# 3_cyber60-alps_mcu.net
KiCad netlist of a schematic drawn in Altium Designer
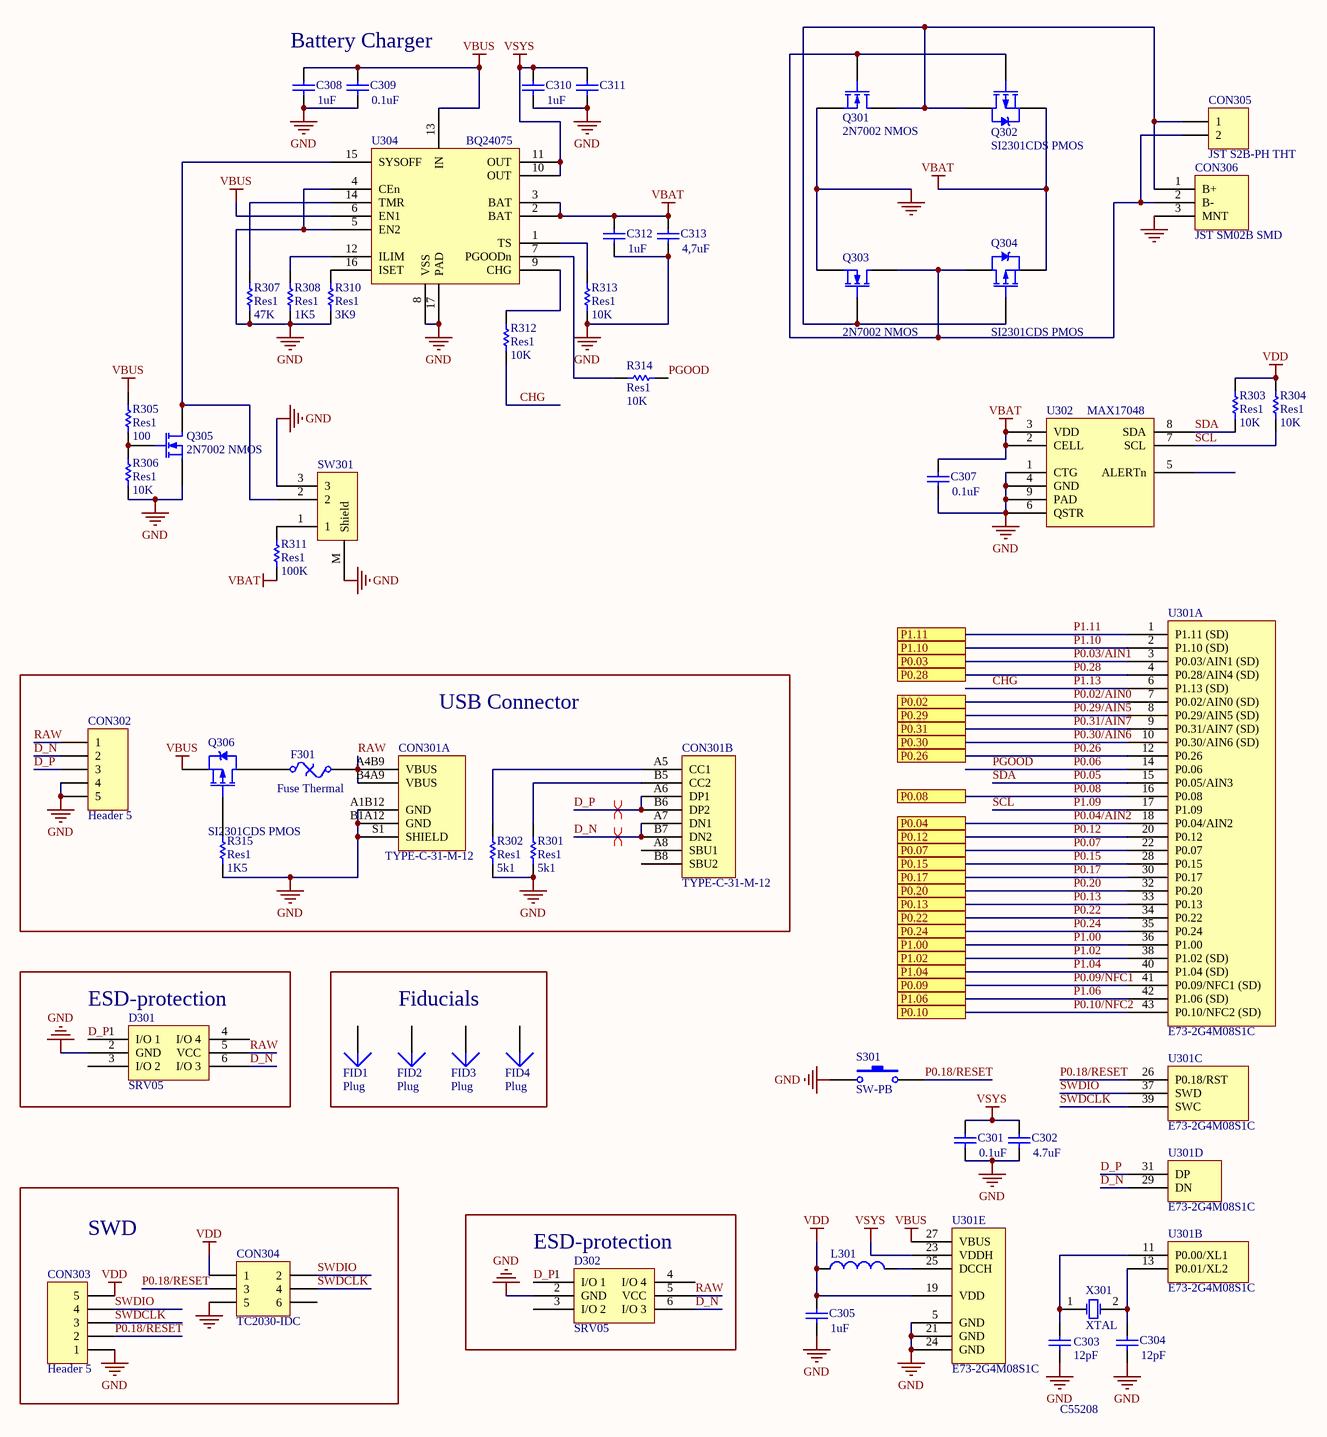
[diagram p0: 3_cyber60-alps_mcu.SchDoc]

(export (version "E")
  (design (tool "Eeschema 10.0.6"))
  (components
    (comp (ref "C301")
      (value "0.1uF")
      (footprint "C0603[1608]")
      (description "Capacitor")
      (fields (field (name "LCSC PART #") "C14663") (field (name "MRF.PART") "CC0603KRX7R9BB104"))
      (libsource (lib "Miscellaneous Devices") (part "Cap"))
    )
    (comp (ref "C302")
      (value "4.7uF")
      (footprint "C0603[1608]")
      (description "Capacitor")
      (fields (field (name "LCSC PART #") "C19666") (field (name "MRF.PART") "CL10A475KO8NNNC"))
      (libsource (lib "Miscellaneous Devices") (part "Cap"))
    )
    (comp (ref "C303")
      (value "12pF")
      (footprint "C0402[1005]")
      (description "Capacitor")
      (fields (field (name "LCSC PART #") "C1547") (field (name "MRF.PART") "0402CG120J500NT"))
      (libsource (lib "Miscellaneous Devices") (part "Cap"))
    )
    (comp (ref "C304")
      (value "12pF")
      (footprint "C0402[1005]")
      (description "Capacitor")
      (fields (field (name "LCSC PART #") "C1547") (field (name "MRF.PART") "0402CG120J500NT"))
      (libsource (lib "Miscellaneous Devices") (part "Cap"))
    )
    (comp (ref "C305")
      (value "1uF")
      (footprint "C0603[1608]")
      (description "Capacitor")
      (fields (field (name "LCSC PART #") "C15849") (field (name "MRF.PART") "CL10A105KB8NNNC"))
      (libsource (lib "Miscellaneous Devices") (part "Cap"))
    )
    (comp (ref "C307")
      (value "0.1uF")
      (footprint "C0603[1608]")
      (description "Capacitor")
      (fields (field (name "LCSC PART #") "C14663") (field (name "MRF.PART") "CC0603KRX7R9BB104"))
      (libsource (lib "Miscellaneous Devices") (part "Cap"))
    )
    (comp (ref "C308")
      (value "1uF")
      (footprint "C0603[1608]")
      (description "Capacitor")
      (fields (field (name "LCSC PART #") "C15849") (field (name "MRF.PART") "CL10A105KB8NNNC"))
      (libsource (lib "Miscellaneous Devices") (part "Cap"))
    )
    (comp (ref "C309")
      (value "0.1uF")
      (footprint "C0603[1608]")
      (description "Capacitor")
      (fields (field (name "LCSC PART #") "C14663") (field (name "MRF.PART") "CC0603KRX7R9BB104"))
      (libsource (lib "Miscellaneous Devices") (part "Cap"))
    )
    (comp (ref "C310")
      (value "1uF")
      (footprint "C0603[1608]")
      (description "Capacitor")
      (fields (field (name "LCSC PART #") "C15849") (field (name "MRF.PART") "CL10A105KB8NNNC"))
      (libsource (lib "Miscellaneous Devices") (part "Cap"))
    )
    (comp (ref "C311")
      (value "~")
      (footprint "C0603[1608]")
      (description "Capacitor")
      (fields (field (name "LCSC PART #") "C19666") (field (name "MRF.PART") "CL10A475KO8NNNC"))
      (libsource (lib "Miscellaneous Devices") (part "Cap"))
    )
    (comp (ref "C312")
      (value "1uF")
      (footprint "C0603[1608]")
      (description "Capacitor")
      (fields (field (name "LCSC PART #") "C15849") (field (name "MRF.PART") "CL10A105KB8NNNC"))
      (libsource (lib "Miscellaneous Devices") (part "Cap"))
    )
    (comp (ref "C313")
      (value "4,7uF")
      (footprint "C0603[1608]")
      (description "Capacitor")
      (fields (field (name "LCSC PART #") "C19666") (field (name "MRF.PART") "CL10A475KO8NNNC"))
      (libsource (lib "Miscellaneous Devices") (part "Cap"))
    )
    (comp (ref "CON301")
      (value "TYPE-C-31-M-12")
      (footprint "TYPE-C-31-M-12")
      (fields (field (name "MFG") "Korean Hroparts Elec") (field (name "LCSC PART #") "C165948"))
      (libsource (lib "Schlib1") (part "TYPE-C-31-M-12"))
    )
    (comp (ref "CON302")
      (value "Header 5")
      (footprint "UDB_COMBO_JST_MOLEX")
      (description "JST for USB daughter board")
      (fields (field (name "MFG") "JST Sales America Inc.") (field (name "LCSC PART #") "C160404"))
      (libsource (lib "Miscellaneous Connectors") (part "Header 5"))
    )
    (comp (ref "CON303")
      (value "Header 5")
      (footprint "HDR1X5")
      (description "Header, 5-Pin")
      (libsource (lib "") (part "Header 5_1"))
    )
    (comp (ref "CON304")
      (value "TC2030-IDC")
      (footprint "TC2030-IDC-NL")
      (description "Header, 3-Pin, Dual row")
      (libsource (lib "Miscellaneous Connectors") (part "Header 3X2"))
    )
    (comp (ref "CON305")
      (value "JST S2B-PH THT")
      (footprint "Keebs:JST S2B-PH-K(LF)(SN)")
      (description "Header, 2-Pin")
      (fields (field (name "LCSC PART #") "C265016") (field (name "MRF.PART") "S2B-PH-K(LF)(SN)"))
      (libsource (lib "Miscellaneous Connectors") (part "Header 2"))
    )
    (comp (ref "CON306")
      (value "JST SM02B SMD")
      (footprint "JST SM02B-SRSS-TB")
      (fields (field (name "LCSC PART #") "C160402") (field (name "MRF.PART") "SM02B-SRSS-TB(LF)(SN)"))
      (libsource (lib "Keebs") (part "JST S2B-PH-SM4-TB"))
    )
    (comp (ref "D301")
      (value "SRV05")
      (footprint "SOT-23-6")
      (fields (field (name "LCSC PART #") "C85364") (field (name "MRF.PART") "SRV05-4-P-T7"))
      (libsource (lib "Keebs") (part "SRV05"))
    )
    (comp (ref "D302")
      (value "SRV05")
      (footprint "SOT-23-6")
      (fields (field (name "LCSC PART #") "C85364") (field (name "MRF.PART") "SRV05-4-P-T7"))
      (libsource (lib "Keebs") (part "SRV05"))
    )
    (comp (ref "F301")
      (value "Fuse Thermal")
      (footprint "C1206[3216]")
      (description "Thermal Fuse")
      (fields (field (name "MFG") "Bel Fuse Inc.") (field (name "LCSC PART #") "C135338"))
      (libsource (lib "Miscellaneous Devices") (part "Fuse Thermal"))
    )
    (comp (ref "FID1")
      (value "Plug")
      (footprint "Fiducial_Nordic")
      (libsource (lib "Miscellaneous Connectors") (part "Plug"))
    )
    (comp (ref "FID2")
      (value "Plug")
      (footprint "Fiducial_Nordic")
      (libsource (lib "Miscellaneous Connectors") (part "Plug"))
    )
    (comp (ref "FID3")
      (value "Plug")
      (footprint "Fiducial_Nordic")
      (libsource (lib "Miscellaneous Connectors") (part "Plug"))
    )
    (comp (ref "FID4")
      (value "Plug")
      (footprint "Fiducial_Nordic")
      (libsource (lib "Miscellaneous Connectors") (part "Plug"))
    )
    (comp (ref "L301")
      (value "Inductor")
      (footprint "L0603[1608]")
      (fields (field (name "LCSC PART #") "C92982") (field (name "MRF.PART") "CBMF1608T100K"))
      (libsource (lib "Simulation Generic Components") (part "Inductor"))
    )
    (comp (ref "Q301")
      (value "2N7002 NMOS")
      (footprint "SOT-23-3")
      (description "N-Channel MOSFET")
      (fields (field (name "LCSC PART #") "C8545") (field (name "MRF.PART") "2N7002"))
      (libsource (lib "Miscellaneous Devices") (part "MOSFET-N"))
    )
    (comp (ref "Q302")
      (value "SI2301CDS PMOS")
      (footprint "SOT-23-3")
      (description "P-Channel Power MOSFET")
      (fields (field (name "MRF.PART") "SI2301CDS-T1-GE3") (field (name "LCSC PART #") "C10487"))
      (libsource (lib "Miscellaneous Devices") (part "PMOS-2"))
    )
    (comp (ref "Q303")
      (value "2N7002 NMOS")
      (footprint "SOT-23-3")
      (description "N-Channel MOSFET")
      (fields (field (name "LCSC PART #") "C8545") (field (name "MRF.PART") "2N7002"))
      (libsource (lib "Miscellaneous Devices") (part "MOSFET-N"))
    )
    (comp (ref "Q304")
      (value "SI2301CDS PMOS")
      (footprint "SOT-23-3")
      (description "P-Channel Power MOSFET")
      (fields (field (name "MRF.PART") "SI2301CDS-T1-GE3") (field (name "LCSC PART #") "C10487"))
      (libsource (lib "Miscellaneous Devices") (part "PMOS-2"))
    )
    (comp (ref "Q305")
      (value "2N7002 NMOS")
      (footprint "SOT-23-3")
      (description "N-Channel MOSFET")
      (fields (field (name "LCSC PART #") "C8545") (field (name "MRF.PART") "2N7002"))
      (libsource (lib "Miscellaneous Devices") (part "MOSFET-N"))
    )
    (comp (ref "Q306")
      (value "SI2301CDS PMOS")
      (footprint "SOT-23-3")
      (description "P-Channel Power MOSFET")
      (fields (field (name "MRF.PART") "SI2301CDS-T1-GE3") (field (name "LCSC PART #") "C10487"))
      (libsource (lib "Miscellaneous Devices") (part "PMOS-2"))
    )
    (comp (ref "R301")
      (value "Res1")
      (footprint "R0603[1608]")
      (description "Resistor")
      (fields
        (field (name "ALTIUM_VALUE") "5k1")
        (field (name "MFG") "Panasonic Electronic Components")
        (field (name "LCSC PART #") "C23186")
      )
      (libsource (lib "Miscellaneous Devices") (part "Res1"))
    )
    (comp (ref "R302")
      (value "Res1")
      (footprint "R0603[1608]")
      (description "Resistor")
      (fields
        (field (name "ALTIUM_VALUE") "5k1")
        (field (name "MFG") "Panasonic Electronic Components")
        (field (name "LCSC PART #") "C23186")
      )
      (libsource (lib "Miscellaneous Devices") (part "Res1"))
    )
    (comp (ref "R303")
      (value "Res1")
      (footprint "R0603[1608]")
      (description "Resistor")
      (fields
        (field (name "ALTIUM_VALUE") "10K")
        (field (name "LCSC PART #") "C25804")
        (field (name "MRF.PART") "0603WAF1002T5E")
      )
      (libsource (lib "Miscellaneous Devices") (part "Res1"))
    )
    (comp (ref "R304")
      (value "Res1")
      (footprint "R0603[1608]")
      (description "Resistor")
      (fields
        (field (name "ALTIUM_VALUE") "10K")
        (field (name "LCSC PART #") "C25804")
        (field (name "MRF.PART") "0603WAF1002T5E")
      )
      (libsource (lib "Miscellaneous Devices") (part "Res1"))
    )
    (comp (ref "R305")
      (value "Res1")
      (footprint "R0603[1608]")
      (description "Resistor")
      (fields
        (field (name "ALTIUM_VALUE") "100")
        (field (name "LCSC PART #") "C22775")
        (field (name "MRF.PART") "0603WAF1000T5E")
      )
      (libsource (lib "Miscellaneous Devices") (part "Res1"))
    )
    (comp (ref "R306")
      (value "Res1")
      (footprint "R0603[1608]")
      (description "Resistor")
      (fields
        (field (name "ALTIUM_VALUE") "10K")
        (field (name "LCSC PART #") "C25804")
        (field (name "MRF.PART") "0603WAF1002T5E")
      )
      (libsource (lib "Miscellaneous Devices") (part "Res1"))
    )
    (comp (ref "R307")
      (value "Res1")
      (footprint "R0603[1608]")
      (description "Resistor")
      (fields
        (field (name "ALTIUM_VALUE") "47K")
        (field (name "LCSC PART #") "C25819")
        (field (name "MRF.PART") "0603WAF4702T5E")
      )
      (libsource (lib "Miscellaneous Devices") (part "Res1"))
    )
    (comp (ref "R308")
      (value "Res1")
      (footprint "R0603[1608]")
      (description "Resistor")
      (fields
        (field (name "ALTIUM_VALUE") "1K5")
        (field (name "LCSC PART #") "C22843")
        (field (name "MRF.PART") "0603WAF1501T5E")
      )
      (libsource (lib "Miscellaneous Devices") (part "Res1"))
    )
    (comp (ref "R310")
      (value "Res1")
      (footprint "R0603[1608]")
      (description "Resistor")
      (fields
        (field (name "ALTIUM_VALUE") "3K9")
        (field (name "LCSC PART #") "C23018")
        (field (name "MRF.PART") "0603WAF3901T5E")
      )
      (libsource (lib "Miscellaneous Devices") (part "Res1"))
    )
    (comp (ref "R311")
      (value "Res1")
      (footprint "R0603[1608]")
      (description "Resistor")
      (fields
        (field (name "ALTIUM_VALUE") "100K")
        (field (name "LCSC PART #") "C25804")
        (field (name "MRF.PART") "0603WAF1002T5E")
      )
      (libsource (lib "Miscellaneous Devices") (part "Res1"))
    )
    (comp (ref "R312")
      (value "Res1")
      (footprint "R0603[1608]")
      (description "Resistor")
      (fields
        (field (name "ALTIUM_VALUE") "10K")
        (field (name "LCSC PART #") "C25804")
        (field (name "MRF.PART") "0603WAF1002T5E")
      )
      (libsource (lib "Miscellaneous Devices") (part "Res1"))
    )
    (comp (ref "R313")
      (value "Res1")
      (footprint "R0603[1608]")
      (description "Resistor")
      (fields
        (field (name "ALTIUM_VALUE") "10K")
        (field (name "LCSC PART #") "C25804")
        (field (name "MRF.PART") "0603WAF1002T5E")
      )
      (libsource (lib "Miscellaneous Devices") (part "Res1"))
    )
    (comp (ref "R314")
      (value "Res1")
      (footprint "R0603[1608]")
      (description "Resistor")
      (fields
        (field (name "ALTIUM_VALUE") "10K")
        (field (name "LCSC PART #") "C25804")
        (field (name "MRF.PART") "0603WAF1002T5E")
      )
      (libsource (lib "Miscellaneous Devices") (part "Res1"))
    )
    (comp (ref "R315")
      (value "Res1")
      (footprint "R0603[1608]")
      (description "Resistor")
      (fields
        (field (name "ALTIUM_VALUE") "1K5")
        (field (name "LCSC PART #") "C22843")
        (field (name "MRF.PART") "0603WAF1501T5E")
      )
      (libsource (lib "Miscellaneous Devices") (part "Res1"))
    )
    (comp (ref "S301")
      (value "SW-PB")
      (footprint "XKB Switch")
      (description "Switch")
      (fields (field (name "MRF.PART") "TS-1187A-C-D-B") (field (name "LCSC PART #") "C318888"))
      (libsource (lib "Miscellaneous Devices") (part "SW-PB"))
    )
    (comp (ref "SW301")
      (value "Korean Hroparts Elec K3-1296S-E2")
      (footprint "Korean Hroparts Elec K3-1296S-E2")
      (fields (field (name "LCSC PART #") "C136659"))
      (libsource (lib "Keebs") (part "Korean Hroparts Elec K3-1296S-E2"))
    )
    (comp (ref "U301")
      (value "E73-2G4M08S1C")
      (footprint "E73-2G4M08S1C")
      (fields (field (name "LCSC PART #") "C356849"))
      (libsource (lib "Keebs") (part "E73-2G4M08S1C"))
    )
    (comp (ref "U302")
      (value "MAX17048")
      (footprint "8TDFN")
      (fields (field (name "LCSC PART #") "C2682616") (field (name "MRF.PART") "MAX17048G+T10"))
      (libsource (lib "Keebs") (part "MAX17048"))
    )
    (comp (ref "U304")
      (value "BQ24075")
      (footprint "QFN16")
      (fields (field (name "LCSC PART #") "C15464") (field (name "MRF.PART") "BQ24075RGTR"))
      (libsource (lib "Keebs") (part "BQ24075"))
    )
    (comp (ref "X301")
      (value "XTAL")
      (footprint "XTAL-2012")
      (description "Crystal Oscillator")
      (fields (field (name "LCSC PART #") "C55208") (field (name "MRF.PART") "X1A0000610002"))
      (libsource (lib "Miscellaneous Devices") (part "XTAL"))
    )
  )
  (nets
    (net (code "1") (name "/CHG") (class "Default")
      (node (ref "R312") (pin "2") (pinfunction "2_2") (pintype "passive"))
      (node (ref "U301") (pin "6") (pinfunction "P1.13_(SD)_6") (pintype "passive"))
    )
    (net (code "2") (name "/D_N") (class "Default")
      (node (ref "CON301") (pin "A7") (pinfunction "DN1_A7") (pintype "passive"))
      (node (ref "CON301") (pin "B7") (pinfunction "DN2_B7") (pintype "passive"))
      (node (ref "CON302") (pin "2") (pinfunction "2_2") (pintype "passive"))
      (node (ref "D301") (pin "6") (pinfunction "I/O_3_6") (pintype "passive"))
      (node (ref "D302") (pin "6") (pinfunction "I/O_3_6") (pintype "passive"))
      (node (ref "U301") (pin "29") (pinfunction "DN_29") (pintype "passive"))
    )
    (net (code "3") (name "/D_P") (class "Default")
      (node (ref "CON301") (pin "A6") (pinfunction "DP1_A6") (pintype "passive"))
      (node (ref "CON301") (pin "B6") (pinfunction "DP2_B6") (pintype "passive"))
      (node (ref "CON302") (pin "3") (pinfunction "3_3") (pintype "passive"))
      (node (ref "D301") (pin "1") (pinfunction "I/O_1_1") (pintype "passive"))
      (node (ref "D302") (pin "1") (pinfunction "I/O_1_1") (pintype "passive"))
      (node (ref "U301") (pin "31") (pinfunction "DP_31") (pintype "passive"))
    )
    (net (code "4") (name "/P0.02{slash}AIN0") (class "Default")
      (node (ref "U301") (pin "7") (pinfunction "P0.02/AIN0_(SD)_7") (pintype "passive"))
    )
    (net (code "5") (name "/P0.03{slash}AIN1") (class "Default")
      (node (ref "U301") (pin "3") (pinfunction "P0.03/AIN1_(SD)_3") (pintype "passive"))
    )
    (net (code "6") (name "/P0.04{slash}AIN2") (class "Default")
      (node (ref "U301") (pin "18") (pinfunction "P0.04/AIN2_18") (pintype "passive"))
    )
    (net (code "7") (name "/P0.05") (class "Default")
      (node (ref "R303") (pin "2") (pinfunction "2_2") (pintype "passive"))
      (node (ref "U301") (pin "15") (pinfunction "P0.05/AIN3_15") (pintype "passive"))
      (node (ref "U302") (pin "8") (pinfunction "SDA_8") (pintype "passive"))
    )
    (net (code "8") (name "/P0.06") (class "Default")
      (node (ref "R314") (pin "2") (pinfunction "2_2") (pintype "passive"))
      (node (ref "U301") (pin "14") (pinfunction "P0.06_14") (pintype "passive"))
    )
    (net (code "9") (name "/P0.07") (class "Default")
      (node (ref "U301") (pin "22") (pinfunction "P0.07_22") (pintype "passive"))
    )
    (net (code "10") (name "/P0.08") (class "Default")
      (node (ref "U301") (pin "16") (pinfunction "P0.08_16") (pintype "passive"))
    )
    (net (code "11") (name "/P0.09{slash}NFC1") (class "Default")
      (node (ref "U301") (pin "41") (pinfunction "P0.09/NFC1_(SD)_41") (pintype "passive"))
    )
    (net (code "12") (name "/P0.10{slash}NFC2") (class "Default")
      (node (ref "U301") (pin "43") (pinfunction "P0.10/NFC2_(SD)_43") (pintype "passive"))
    )
    (net (code "13") (name "/P0.12") (class "Default")
      (node (ref "U301") (pin "20") (pinfunction "P0.12_20") (pintype "passive"))
    )
    (net (code "14") (name "/P0.13") (class "Default")
      (node (ref "U301") (pin "33") (pinfunction "P0.13_33") (pintype "passive"))
    )
    (net (code "15") (name "/P0.15") (class "Default")
      (node (ref "U301") (pin "28") (pinfunction "P0.15_28") (pintype "passive"))
    )
    (net (code "16") (name "/P0.17") (class "Default")
      (node (ref "U301") (pin "30") (pinfunction "P0.17_30") (pintype "passive"))
    )
    (net (code "17") (name "/P0.18{slash}RESET") (class "Default")
      (node (ref "CON303") (pin "2") (pinfunction "2_2") (pintype "passive"))
      (node (ref "CON304") (pin "3") (pinfunction "3_3") (pintype "passive"))
      (node (ref "S301") (pin "2") (pinfunction "2_2") (pintype "passive"))
      (node (ref "U301") (pin "26") (pinfunction "P0.18/RST_26") (pintype "passive"))
    )
    (net (code "18") (name "/P0.20") (class "Default")
      (node (ref "U301") (pin "32") (pinfunction "P0.20_32") (pintype "passive"))
    )
    (net (code "19") (name "/P0.22") (class "Default")
      (node (ref "U301") (pin "34") (pinfunction "P0.22_34") (pintype "passive"))
    )
    (net (code "20") (name "/P0.24") (class "Default")
      (node (ref "U301") (pin "35") (pinfunction "P0.24_35") (pintype "passive"))
    )
    (net (code "21") (name "/P0.26") (class "Default")
      (node (ref "U301") (pin "12") (pinfunction "P0.26_12") (pintype "passive"))
    )
    (net (code "22") (name "/P0.28") (class "Default")
      (node (ref "U301") (pin "4") (pinfunction "P0.28/AIN4_(SD)_4") (pintype "passive"))
    )
    (net (code "23") (name "/P0.29{slash}AIN5") (class "Default")
      (node (ref "U301") (pin "8") (pinfunction "P0.29/AIN5_(SD)_8") (pintype "passive"))
    )
    (net (code "24") (name "/P0.30{slash}AIN6") (class "Default")
      (node (ref "U301") (pin "10") (pinfunction "P0.30/AIN6_(SD)_10") (pintype "passive"))
    )
    (net (code "25") (name "/P0.31{slash}AIN7") (class "Default")
      (node (ref "U301") (pin "9") (pinfunction "P0.31/AIN7_(SD)_9") (pintype "passive"))
    )
    (net (code "26") (name "/P1.00") (class "Default")
      (node (ref "U301") (pin "36") (pinfunction "P1.00_36") (pintype "passive"))
    )
    (net (code "27") (name "/P1.02") (class "Default")
      (node (ref "U301") (pin "38") (pinfunction "P1.02_(SD)_38") (pintype "passive"))
    )
    (net (code "28") (name "/P1.04") (class "Default")
      (node (ref "U301") (pin "40") (pinfunction "P1.04_(SD)_40") (pintype "passive"))
    )
    (net (code "29") (name "/P1.06") (class "Default")
      (node (ref "U301") (pin "42") (pinfunction "P1.06_(SD)_42") (pintype "passive"))
    )
    (net (code "30") (name "/P1.09") (class "Default")
      (node (ref "R304") (pin "2") (pinfunction "2_2") (pintype "passive"))
      (node (ref "U301") (pin "17") (pinfunction "P1.09_17") (pintype "passive"))
      (node (ref "U302") (pin "7") (pinfunction "SCL_7") (pintype "passive"))
    )
    (net (code "31") (name "/P1.10") (class "Default")
      (node (ref "U301") (pin "2") (pinfunction "P1.10_(SD)_2") (pintype "passive"))
    )
    (net (code "32") (name "/P1.11") (class "Default")
      (node (ref "U301") (pin "1") (pinfunction "P1.11_(SD)_1") (pintype "passive"))
    )
    (net (code "33") (name "/RAW") (class "Default")
      (node (ref "CON301") (pin "A4B9") (pinfunction "VBUS_A4B9") (pintype "passive"))
      (node (ref "CON301") (pin "B4A9") (pinfunction "VBUS_B4A9") (pintype "passive"))
      (node (ref "CON302") (pin "1") (pinfunction "1_1") (pintype "passive"))
      (node (ref "D301") (pin "5") (pinfunction "VCC_5") (pintype "passive"))
      (node (ref "D302") (pin "5") (pinfunction "VCC_5") (pintype "passive"))
      (node (ref "F301") (pin "2") (pinfunction "2_2") (pintype "passive"))
    )
    (net (code "34") (name "/SWDCLK") (class "Default")
      (node (ref "CON303") (pin "3") (pinfunction "3_3") (pintype "passive"))
      (node (ref "CON304") (pin "4") (pinfunction "4_4") (pintype "passive"))
      (node (ref "U301") (pin "39") (pinfunction "SWC_39") (pintype "passive"))
    )
    (net (code "35") (name "/SWDIO") (class "Default")
      (node (ref "CON303") (pin "4") (pinfunction "4_4") (pintype "passive"))
      (node (ref "CON304") (pin "2") (pinfunction "2_2") (pintype "passive"))
      (node (ref "U301") (pin "37") (pinfunction "SWD_37") (pintype "passive"))
    )
    (net (code "36") (name "GND") (class "Default")
      (node (ref "C301") (pin "1") (pinfunction "1_1") (pintype "passive"))
      (node (ref "C302") (pin "1") (pinfunction "1_1") (pintype "passive"))
      (node (ref "C303") (pin "1") (pinfunction "1_1") (pintype "passive"))
      (node (ref "C304") (pin "1") (pinfunction "1_1") (pintype "passive"))
      (node (ref "C305") (pin "1") (pinfunction "1_1") (pintype "passive"))
      (node (ref "C307") (pin "1") (pinfunction "1_1") (pintype "passive"))
      (node (ref "C308") (pin "1") (pinfunction "1_1") (pintype "passive"))
      (node (ref "C309") (pin "1") (pinfunction "1_1") (pintype "passive"))
      (node (ref "C310") (pin "1") (pinfunction "1_1") (pintype "passive"))
      (node (ref "C311") (pin "1") (pinfunction "1_1") (pintype "passive"))
      (node (ref "C312") (pin "1") (pinfunction "1_1") (pintype "passive"))
      (node (ref "C313") (pin "1") (pinfunction "1_1") (pintype "passive"))
      (node (ref "CON301") (pin "A1B12") (pinfunction "GND_A1B12") (pintype "passive"))
      (node (ref "CON301") (pin "B1A12") (pinfunction "GND_B1A12") (pintype "passive"))
      (node (ref "CON301") (pin "S1") (pinfunction "SHIELD_S1") (pintype "passive"))
      (node (ref "CON302") (pin "4") (pinfunction "4_4") (pintype "passive"))
      (node (ref "CON302") (pin "5") (pinfunction "5_5") (pintype "passive"))
      (node (ref "CON303") (pin "1") (pinfunction "1_1") (pintype "passive"))
      (node (ref "CON304") (pin "5") (pinfunction "5_5") (pintype "passive"))
      (node (ref "CON306") (pin "3") (pinfunction "MNT_3") (pintype "passive"))
      (node (ref "D301") (pin "2") (pinfunction "GND_2") (pintype "passive"))
      (node (ref "D302") (pin "2") (pinfunction "GND_2") (pintype "passive"))
      (node (ref "Q301") (pin "2") (pinfunction "S_2") (pintype "passive"))
      (node (ref "Q303") (pin "2") (pinfunction "S_2") (pintype "passive"))
      (node (ref "Q305") (pin "2") (pinfunction "S_2") (pintype "passive"))
      (node (ref "R301") (pin "2") (pinfunction "2_2") (pintype "passive"))
      (node (ref "R302") (pin "2") (pinfunction "2_2") (pintype "passive"))
      (node (ref "R306") (pin "2") (pinfunction "2_2") (pintype "passive"))
      (node (ref "R307") (pin "2") (pinfunction "2_2") (pintype "passive"))
      (node (ref "R308") (pin "2") (pinfunction "2_2") (pintype "passive"))
      (node (ref "R310") (pin "2") (pinfunction "2_2") (pintype "passive"))
      (node (ref "R313") (pin "2") (pinfunction "2_2") (pintype "passive"))
      (node (ref "R315") (pin "2") (pinfunction "2_2") (pintype "passive"))
      (node (ref "S301") (pin "1") (pinfunction "1_1") (pintype "passive"))
      (node (ref "SW301") (pin "3") (pinfunction "3_3") (pintype "passive"))
      (node (ref "SW301") (pin "M") (pinfunction "Shield_M") (pintype "passive"))
      (node (ref "U301") (pin "21") (pinfunction "GND_21") (pintype "passive"))
      (node (ref "U301") (pin "24") (pinfunction "GND_24") (pintype "passive"))
      (node (ref "U301") (pin "5") (pinfunction "GND_5") (pintype "passive"))
      (node (ref "U302") (pin "1") (pinfunction "CTG_1") (pintype "passive"))
      (node (ref "U302") (pin "4") (pinfunction "GND_4") (pintype "passive"))
      (node (ref "U302") (pin "6") (pinfunction "QSTR_6") (pintype "passive"))
      (node (ref "U302") (pin "9") (pinfunction "PAD_9") (pintype "passive"))
      (node (ref "U304") (pin "17") (pinfunction "PAD_17") (pintype "passive"))
      (node (ref "U304") (pin "4") (pinfunction "CEn_4") (pintype "passive"))
      (node (ref "U304") (pin "5") (pinfunction "EN2_5") (pintype "passive"))
      (node (ref "U304") (pin "8") (pinfunction "VSS_8") (pintype "passive"))
    )
    (net (code "37") (name "Net-(CON301B-CC1)") (class "Default")
      (node (ref "CON301") (pin "A5") (pinfunction "CC1_A5") (pintype "passive"))
      (node (ref "R302") (pin "1") (pinfunction "1_1") (pintype "passive"))
    )
    (net (code "38") (name "Net-(CON301B-CC2)") (class "Default")
      (node (ref "CON301") (pin "B5") (pinfunction "CC2_B5") (pintype "passive"))
      (node (ref "R301") (pin "1") (pinfunction "1_1") (pintype "passive"))
    )
    (net (code "39") (name "Net-(CON306-B+)") (class "Default")
      (node (ref "CON305") (pin "1") (pinfunction "1_1") (pintype "passive"))
      (node (ref "CON306") (pin "1") (pinfunction "B+_1") (pintype "passive"))
      (node (ref "Q301") (pin "3") (pinfunction "D_3") (pintype "passive"))
      (node (ref "Q302") (pin "3") (pinfunction "D_3") (pintype "passive"))
      (node (ref "Q303") (pin "1") (pinfunction "G_1") (pintype "passive"))
      (node (ref "Q304") (pin "1") (pinfunction "G_1") (pintype "passive"))
    )
    (net (code "40") (name "Net-(CON306-B-)") (class "Default")
      (node (ref "CON305") (pin "2") (pinfunction "2_2") (pintype "passive"))
      (node (ref "CON306") (pin "2") (pinfunction "B-_2") (pintype "passive"))
      (node (ref "Q301") (pin "1") (pinfunction "G_1") (pintype "passive"))
      (node (ref "Q302") (pin "1") (pinfunction "G_1") (pintype "passive"))
      (node (ref "Q303") (pin "3") (pinfunction "D_3") (pintype "passive"))
      (node (ref "Q304") (pin "3") (pinfunction "D_3") (pintype "passive"))
    )
    (net (code "41") (name "Net-(Q305-D)") (class "Default")
      (node (ref "Q305") (pin "3") (pinfunction "D_3") (pintype "passive"))
      (node (ref "SW301") (pin "2") (pinfunction "2_2") (pintype "passive"))
      (node (ref "U304") (pin "15") (pinfunction "SYSOFF_15") (pintype "passive"))
    )
    (net (code "42") (name "Net-(Q305-G)") (class "Default")
      (node (ref "Q305") (pin "1") (pinfunction "G_1") (pintype "passive"))
      (node (ref "R305") (pin "2") (pinfunction "2_2") (pintype "passive"))
      (node (ref "R306") (pin "1") (pinfunction "1_1") (pintype "passive"))
    )
    (net (code "43") (name "Net-(Q306-D)") (class "Default")
      (node (ref "F301") (pin "1") (pinfunction "1_1") (pintype "passive"))
      (node (ref "Q306") (pin "3") (pinfunction "D_3") (pintype "passive"))
    )
    (net (code "44") (name "Net-(Q306-G)") (class "Default")
      (node (ref "Q306") (pin "1") (pinfunction "G_1") (pintype "passive"))
      (node (ref "R315") (pin "1") (pinfunction "1_1") (pintype "passive"))
    )
    (net (code "45") (name "Net-(R311-Pad1)") (class "Default")
      (node (ref "R311") (pin "1") (pinfunction "1_1") (pintype "passive"))
      (node (ref "SW301") (pin "1") (pinfunction "1_1") (pintype "passive"))
    )
    (net (code "46") (name "Net-(U301B-P0.00{slash}XL1)") (class "Default")
      (node (ref "C303") (pin "2") (pinfunction "2_2") (pintype "passive"))
      (node (ref "U301") (pin "11") (pinfunction "P0.00/XL1_11") (pintype "passive"))
      (node (ref "X301") (pin "1") (pinfunction "OSC1_1") (pintype "passive"))
    )
    (net (code "47") (name "Net-(U301B-P0.01{slash}XL2)") (class "Default")
      (node (ref "C304") (pin "2") (pinfunction "2_2") (pintype "passive"))
      (node (ref "U301") (pin "13") (pinfunction "P0.01/XL2_13") (pintype "passive"))
      (node (ref "X301") (pin "2") (pinfunction "OSC2_2") (pintype "passive"))
    )
    (net (code "48") (name "Net-(U301E-DCCH)") (class "Default")
      (node (ref "L301") (pin "2") (pinfunction "2_2") (pintype "passive"))
      (node (ref "U301") (pin "25") (pinfunction "DCCH_25") (pintype "passive"))
    )
    (net (code "49") (name "Net-(U304-CHG)") (class "Default")
      (node (ref "R312") (pin "1") (pinfunction "1_1") (pintype "passive"))
      (node (ref "U304") (pin "9") (pinfunction "CHG_9") (pintype "passive"))
    )
    (net (code "50") (name "Net-(U304-ILIM)") (class "Default")
      (node (ref "R308") (pin "1") (pinfunction "1_1") (pintype "passive"))
      (node (ref "U304") (pin "12") (pinfunction "ILIM_12") (pintype "passive"))
    )
    (net (code "51") (name "Net-(U304-ISET)") (class "Default")
      (node (ref "R310") (pin "1") (pinfunction "1_1") (pintype "passive"))
      (node (ref "U304") (pin "16") (pinfunction "ISET_16") (pintype "passive"))
    )
    (net (code "52") (name "Net-(U304-PGOODn)") (class "Default")
      (node (ref "R314") (pin "1") (pinfunction "1_1") (pintype "passive"))
      (node (ref "U304") (pin "7") (pinfunction "PGOODn_7") (pintype "passive"))
    )
    (net (code "53") (name "Net-(U304-TMR)") (class "Default")
      (node (ref "R307") (pin "1") (pinfunction "1_1") (pintype "passive"))
      (node (ref "U304") (pin "14") (pinfunction "TMR_14") (pintype "passive"))
    )
    (net (code "54") (name "Net-(U304-TS)") (class "Default")
      (node (ref "R313") (pin "1") (pinfunction "1_1") (pintype "passive"))
      (node (ref "U304") (pin "1") (pinfunction "TS_1") (pintype "passive"))
    )
    (net (code "55") (name "VBAT") (class "Default")
      (node (ref "C307") (pin "2") (pinfunction "2_2") (pintype "passive"))
      (node (ref "C312") (pin "2") (pinfunction "2_2") (pintype "passive"))
      (node (ref "C313") (pin "2") (pinfunction "2_2") (pintype "passive"))
      (node (ref "Q302") (pin "2") (pinfunction "S_2") (pintype "passive"))
      (node (ref "Q304") (pin "2") (pinfunction "S_2") (pintype "passive"))
      (node (ref "R311") (pin "2") (pinfunction "2_2") (pintype "passive"))
      (node (ref "U302") (pin "2") (pinfunction "CELL_2") (pintype "passive"))
      (node (ref "U302") (pin "3") (pinfunction "VDD_3") (pintype "passive"))
      (node (ref "U304") (pin "2") (pinfunction "BAT_2") (pintype "passive"))
      (node (ref "U304") (pin "3") (pinfunction "BAT_3") (pintype "passive"))
    )
    (net (code "56") (name "VBUS") (class "Default")
      (node (ref "C308") (pin "2") (pinfunction "2_2") (pintype "passive"))
      (node (ref "C309") (pin "2") (pinfunction "2_2") (pintype "passive"))
      (node (ref "Q306") (pin "2") (pinfunction "S_2") (pintype "passive"))
      (node (ref "R305") (pin "1") (pinfunction "1_1") (pintype "passive"))
      (node (ref "U301") (pin "27") (pinfunction "VBUS_27") (pintype "passive"))
      (node (ref "U304") (pin "13") (pinfunction "IN_13") (pintype "passive"))
      (node (ref "U304") (pin "6") (pinfunction "EN1_6") (pintype "passive"))
    )
    (net (code "57") (name "VDD") (class "Default")
      (node (ref "C305") (pin "2") (pinfunction "2_2") (pintype "passive"))
      (node (ref "CON303") (pin "5") (pinfunction "5_5") (pintype "passive"))
      (node (ref "CON304") (pin "1") (pinfunction "1_1") (pintype "passive"))
      (node (ref "L301") (pin "1") (pinfunction "1_1") (pintype "passive"))
      (node (ref "R303") (pin "1") (pinfunction "1_1") (pintype "passive"))
      (node (ref "R304") (pin "1") (pinfunction "1_1") (pintype "passive"))
      (node (ref "U301") (pin "19") (pinfunction "VDD_19") (pintype "passive"))
    )
    (net (code "58") (name "VSYS") (class "Default")
      (node (ref "C301") (pin "2") (pinfunction "2_2") (pintype "passive"))
      (node (ref "C302") (pin "2") (pinfunction "2_2") (pintype "passive"))
      (node (ref "C310") (pin "2") (pinfunction "2_2") (pintype "passive"))
      (node (ref "C311") (pin "2") (pinfunction "2_2") (pintype "passive"))
      (node (ref "U301") (pin "23") (pinfunction "VDDH_23") (pintype "passive"))
      (node (ref "U304") (pin "10") (pinfunction "OUT_10") (pintype "passive"))
      (node (ref "U304") (pin "11") (pinfunction "OUT_11") (pintype "passive"))
    )
    (net (code "59") (name "unconnected-(CON301B-SBU1-PadA8)") (class "Default")
      (node (ref "CON301") (pin "A8") (pinfunction "SBU1_A8") (pintype "passive"))
    )
    (net (code "60") (name "unconnected-(CON301B-SBU2-PadB8)") (class "Default")
      (node (ref "CON301") (pin "B8") (pinfunction "SBU2_B8") (pintype "passive"))
    )
    (net (code "61") (name "unconnected-(CON304-Pad6)") (class "Default")
      (node (ref "CON304") (pin "6") (pinfunction "6_6") (pintype "passive"))
    )
    (net (code "62") (name "unconnected-(D301-I{slash}O_2-Pad3)") (class "Default")
      (node (ref "D301") (pin "3") (pinfunction "I/O_2_3") (pintype "passive"))
    )
    (net (code "63") (name "unconnected-(D301-I{slash}O_4-Pad4)") (class "Default")
      (node (ref "D301") (pin "4") (pinfunction "I/O_4_4") (pintype "passive"))
    )
    (net (code "64") (name "unconnected-(D302-I{slash}O_2-Pad3)") (class "Default")
      (node (ref "D302") (pin "3") (pinfunction "I/O_2_3") (pintype "passive"))
    )
    (net (code "65") (name "unconnected-(D302-I{slash}O_4-Pad4)") (class "Default")
      (node (ref "D302") (pin "4") (pinfunction "I/O_4_4") (pintype "passive"))
    )
    (net (code "66") (name "unconnected-(FID1-Pad1)") (class "Default")
      (node (ref "FID1") (pin "1") (pinfunction "1_1") (pintype "passive"))
    )
    (net (code "67") (name "unconnected-(FID2-Pad1)") (class "Default")
      (node (ref "FID2") (pin "1") (pinfunction "1_1") (pintype "passive"))
    )
    (net (code "68") (name "unconnected-(FID3-Pad1)") (class "Default")
      (node (ref "FID3") (pin "1") (pinfunction "1_1") (pintype "passive"))
    )
    (net (code "69") (name "unconnected-(FID4-Pad1)") (class "Default")
      (node (ref "FID4") (pin "1") (pinfunction "1_1") (pintype "passive"))
    )
    (net (code "70") (name "unconnected-(U302-ALERTn-Pad5)") (class "Default")
      (node (ref "U302") (pin "5") (pinfunction "ALERTn_5") (pintype "passive"))
    )
  )
)
